# RELAY.net
KiCad netlist of a schematic drawn in Altium Designer
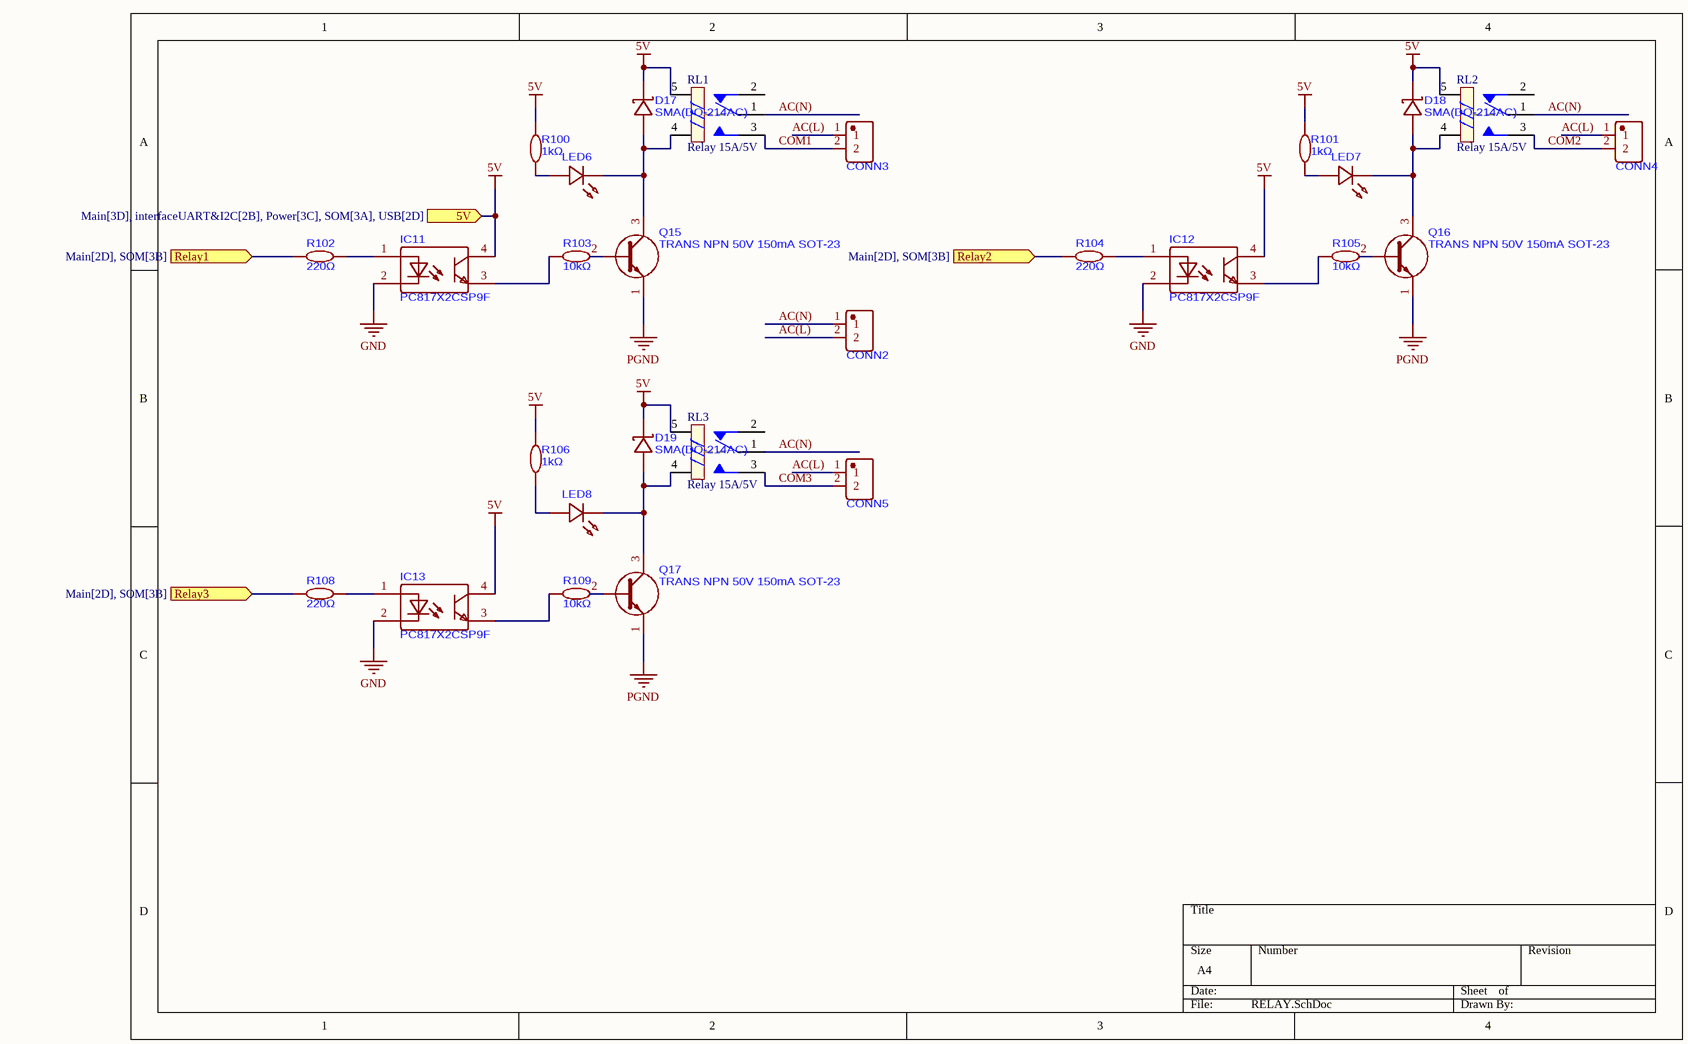
[diagram p0: RELAY.SchDoc]

(export (version "E")
  (design (tool "Eeschema 10.0.6"))
  (components
    (comp (ref "CONN2")
      (value "TERM BLK 2POS 5mm TH")
      (footprint "CONN-TH_P5.00_KF128-5.0-2P")
      (libsource (lib "Schlib2") (part "KF128-5.0-2P"))
    )
    (comp (ref "CONN3")
      (value "TERM BLK 2POS 5mm TH")
      (footprint "CONN-TH_P5.00_KF128-5.0-2P")
      (libsource (lib "Schlib2") (part "KF128-5.0-2P"))
    )
    (comp (ref "CONN4")
      (value "TERM BLK 2POS 5mm TH")
      (footprint "CONN-TH_P5.00_KF128-5.0-2P")
      (libsource (lib "Schlib2") (part "KF128-5.0-2P"))
    )
    (comp (ref "CONN5")
      (value "TERM BLK 2POS 5mm TH")
      (footprint "CONN-TH_P5.00_KF128-5.0-2P")
      (libsource (lib "Schlib2") (part "KF128-5.0-2P"))
    )
    (comp (ref "D17")
      (value "SMA(DO-214AC)")
      (footprint "SMA_L4.4-W2.6-LS5.0-RD")
      (description "80A 40V 500mV@3A 3A SMA(DO-214AC) Single Diodes ROHS")
      (libsource (lib "Schlib2") (part "B340A-13-F"))
    )
    (comp (ref "D18")
      (value "SMA(DO-214AC)")
      (footprint "SMA_L4.4-W2.6-LS5.0-RD")
      (description "80A 40V 500mV@3A 3A SMA(DO-214AC) Single Diodes ROHS")
      (libsource (lib "Schlib2") (part "B340A-13-F"))
    )
    (comp (ref "D19")
      (value "SMA(DO-214AC)")
      (footprint "SMA_L4.4-W2.6-LS5.0-RD")
      (description "80A 40V 500mV@3A 3A SMA(DO-214AC) Single Diodes ROHS")
      (libsource (lib "Schlib2") (part "B340A-13-F"))
    )
    (comp (ref "IC11")
      (value "PC817X2CSP9F")
      (footprint "smd pc817")
      (description "50mA 200mV@20mA,1mA 80V 6V DC SMD-4P Transistor, Photovoltaic Output Optoisolators RoHS")
      (libsource (lib "Schlib2") (part "PC817X2CSP9F"))
    )
    (comp (ref "IC12")
      (value "PC817X2CSP9F")
      (footprint "smd pc817")
      (description "50mA 200mV@20mA,1mA 80V 6V DC SMD-4P Transistor, Photovoltaic Output Optoisolators RoHS")
      (libsource (lib "Schlib2") (part "PC817X2CSP9F"))
    )
    (comp (ref "IC13")
      (value "PC817X2CSP9F")
      (footprint "smd pc817")
      (description "50mA 200mV@20mA,1mA 80V 6V DC SMD-4P Transistor, Photovoltaic Output Optoisolators RoHS")
      (libsource (lib "Schlib2") (part "PC817X2CSP9F"))
    )
    (comp (ref "LED6")
      (value "XL-1608SURC-06")
      (footprint "LED0603-RD_RED")
      (description "20mA 2.3V Red 50mW 0603 LED Indication - Discrete ROHS")
      (libsource (lib "Schlib2") (part "XL-1608SURC-06"))
    )
    (comp (ref "LED7")
      (value "XL-1608SURC-06")
      (footprint "LED0603-RD_RED")
      (description "20mA 2.3V Red 50mW 0603 LED Indication - Discrete ROHS")
      (libsource (lib "Schlib2") (part "XL-1608SURC-06"))
    )
    (comp (ref "LED8")
      (value "XL-1608SURC-06")
      (footprint "LED0603-RD_RED")
      (description "20mA 2.3V Red 50mW 0603 LED Indication - Discrete ROHS")
      (libsource (lib "Schlib2") (part "XL-1608SURC-06"))
    )
    (comp (ref "Q15")
      (value "TRANS NPN 50V 150mA SOT-23")
      (footprint "SOT-23-3_L2.9-W1.3-P1.90-LS2.4-BR")
      (description "200mW 50V 150mA NPN SOT-23 Single Bipolar Transistors RoHS")
      (libsource (lib "Schlib2") (part "2SC1815"))
    )
    (comp (ref "Q16")
      (value "TRANS NPN 50V 150mA SOT-23")
      (footprint "SOT-23-3_L2.9-W1.3-P1.90-LS2.4-BR")
      (description "200mW 50V 150mA NPN SOT-23 Single Bipolar Transistors RoHS")
      (libsource (lib "Schlib2") (part "2SC1815"))
    )
    (comp (ref "Q17")
      (value "TRANS NPN 50V 150mA SOT-23")
      (footprint "SOT-23-3_L2.9-W1.3-P1.90-LS2.4-BR")
      (description "200mW 50V 150mA NPN SOT-23 Single Bipolar Transistors RoHS")
      (libsource (lib "Schlib2") (part "2SC1815"))
    )
    (comp (ref "R100")
      (value "1kΩ")
      (footprint "R0603")
      (description "100mW 1kΩ 50V ±100ppm/℃ Thick Film Resistor ±5% 0603 Chip Resistor - Surface Mount ROHS")
      (libsource (lib "Schlib2") (part "RMC 0603 1K J N"))
    )
    (comp (ref "R101")
      (value "1kΩ")
      (footprint "R0603")
      (description "100mW 1kΩ 50V ±100ppm/℃ Thick Film Resistor ±5% 0603 Chip Resistor - Surface Mount ROHS")
      (libsource (lib "Schlib2") (part "RMC 0603 1K J N"))
    )
    (comp (ref "R102")
      (value "220Ω")
      (footprint "R0603")
      (description "100mW 220Ω 75V ±100ppm/℃ Thick Film Resistor ±1% 0603 Chip Resistor - Surface Mount RoHS")
      (libsource (lib "Schlib2") (part "RC0603FR-07220RL"))
    )
    (comp (ref "R103")
      (value "10kΩ")
      (footprint "R0603")
      (description "100mW 10kΩ 75V ±100ppm/℃ Thick Film Resistor ±1% 0603 Chip Resistor - Surface Mount ROHS")
      (libsource (lib "Schlib2") (part "RC0603FR-0710KL"))
    )
    (comp (ref "R104")
      (value "220Ω")
      (footprint "R0603")
      (description "100mW 220Ω 75V ±100ppm/℃ Thick Film Resistor ±1% 0603 Chip Resistor - Surface Mount RoHS")
      (libsource (lib "Schlib2") (part "RC0603FR-07220RL"))
    )
    (comp (ref "R105")
      (value "10kΩ")
      (footprint "R0603")
      (description "100mW 10kΩ 75V ±100ppm/℃ Thick Film Resistor ±1% 0603 Chip Resistor - Surface Mount ROHS")
      (libsource (lib "Schlib2") (part "RC0603FR-0710KL"))
    )
    (comp (ref "R106")
      (value "1kΩ")
      (footprint "R0603")
      (description "100mW 1kΩ 50V ±100ppm/℃ Thick Film Resistor ±5% 0603 Chip Resistor - Surface Mount ROHS")
      (libsource (lib "Schlib2") (part "RMC 0603 1K J N"))
    )
    (comp (ref "R108")
      (value "220Ω")
      (footprint "R0603")
      (description "100mW 220Ω 75V ±100ppm/℃ Thick Film Resistor ±1% 0603 Chip Resistor - Surface Mount RoHS")
      (libsource (lib "Schlib2") (part "RC0603FR-07220RL"))
    )
    (comp (ref "R109")
      (value "10kΩ")
      (footprint "R0603")
      (description "100mW 10kΩ 75V ±100ppm/℃ Thick Film Resistor ±1% 0603 Chip Resistor - Surface Mount ROHS")
      (libsource (lib "Schlib2") (part "RC0603FR-0710KL"))
    )
    (comp (ref "RL1")
      (value "Relay 15A/5V")
      (footprint "RL-5V-15A")
      (description "Relay SPDT,10A - 5VDC 5 Pin")
      (libsource (lib "Schlib2") (part "SRD-05VDC-SL-C"))
    )
    (comp (ref "RL2")
      (value "Relay 15A/5V")
      (footprint "RL-5V-15A")
      (description "Relay SPDT,10A - 5VDC 5 Pin")
      (libsource (lib "Schlib2") (part "SRD-05VDC-SL-C"))
    )
    (comp (ref "RL3")
      (value "Relay 15A/5V")
      (footprint "RL-5V-15A")
      (description "Relay SPDT,10A - 5VDC 5 Pin")
      (libsource (lib "Schlib2") (part "SRD-05VDC-SL-C"))
    )
  )
  (nets
    (net (code "1") (name "/AC(L)") (class "Default")
      (node (ref "CONN2") (pin "2") (pinfunction "2_2") (pintype "passive"))
      (node (ref "CONN3") (pin "1") (pinfunction "1_1") (pintype "passive"))
      (node (ref "CONN4") (pin "1") (pinfunction "1_1") (pintype "passive"))
      (node (ref "CONN5") (pin "1") (pinfunction "1_1") (pintype "passive"))
    )
    (net (code "2") (name "/AC(N)") (class "Default")
      (node (ref "CONN2") (pin "1") (pinfunction "1_1") (pintype "passive"))
      (node (ref "RL1") (pin "1") (pinfunction "1_1") (pintype "passive"))
      (node (ref "RL2") (pin "1") (pinfunction "1_1") (pintype "passive"))
      (node (ref "RL3") (pin "1") (pinfunction "1_1") (pintype "passive"))
    )
    (net (code "3") (name "/COM1") (class "Default")
      (node (ref "CONN3") (pin "2") (pinfunction "2_2") (pintype "passive"))
      (node (ref "RL1") (pin "3") (pinfunction "3_3") (pintype "passive"))
    )
    (net (code "4") (name "/COM2") (class "Default")
      (node (ref "CONN4") (pin "2") (pinfunction "2_2") (pintype "passive"))
      (node (ref "RL2") (pin "3") (pinfunction "3_3") (pintype "passive"))
    )
    (net (code "5") (name "/COM3") (class "Default")
      (node (ref "CONN5") (pin "2") (pinfunction "2_2") (pintype "passive"))
      (node (ref "RL3") (pin "3") (pinfunction "3_3") (pintype "passive"))
    )
    (net (code "6") (name "/Relay1") (class "Default")
      (node (ref "R102") (pin "1") (pinfunction "1_1") (pintype "passive"))
    )
    (net (code "7") (name "/Relay2") (class "Default")
      (node (ref "R104") (pin "1") (pinfunction "1_1") (pintype "passive"))
    )
    (net (code "8") (name "/Relay3") (class "Default")
      (node (ref "R108") (pin "1") (pinfunction "1_1") (pintype "passive"))
    )
    (net (code "9") (name "5V") (class "Default")
      (node (ref "D17") (pin "1") (pinfunction "K_1") (pintype "passive"))
      (node (ref "D18") (pin "1") (pinfunction "K_1") (pintype "passive"))
      (node (ref "D19") (pin "1") (pinfunction "K_1") (pintype "passive"))
      (node (ref "IC11") (pin "4") (pinfunction "COL_4") (pintype "passive"))
      (node (ref "IC12") (pin "4") (pinfunction "COL_4") (pintype "passive"))
      (node (ref "IC13") (pin "4") (pinfunction "COL_4") (pintype "passive"))
      (node (ref "R100") (pin "2") (pinfunction "2_2") (pintype "passive"))
      (node (ref "R101") (pin "2") (pinfunction "2_2") (pintype "passive"))
      (node (ref "R106") (pin "2") (pinfunction "2_2") (pintype "passive"))
      (node (ref "RL1") (pin "5") (pinfunction "5_5") (pintype "passive"))
      (node (ref "RL2") (pin "5") (pinfunction "5_5") (pintype "passive"))
      (node (ref "RL3") (pin "5") (pinfunction "5_5") (pintype "passive"))
    )
    (net (code "10") (name "GND") (class "Default")
      (node (ref "IC11") (pin "2") (pinfunction "CAT_2") (pintype "passive"))
      (node (ref "IC12") (pin "2") (pinfunction "CAT_2") (pintype "passive"))
      (node (ref "IC13") (pin "2") (pinfunction "CAT_2") (pintype "passive"))
    )
    (net (code "11") (name "Net-(D17-A)") (class "Default")
      (node (ref "D17") (pin "2") (pinfunction "A_2") (pintype "passive"))
      (node (ref "LED6") (pin "1") (pinfunction "K_1") (pintype "passive"))
      (node (ref "Q15") (pin "3") (pintype "passive"))
      (node (ref "RL1") (pin "4") (pinfunction "4_4") (pintype "passive"))
    )
    (net (code "12") (name "Net-(D18-A)") (class "Default")
      (node (ref "D18") (pin "2") (pinfunction "A_2") (pintype "passive"))
      (node (ref "LED7") (pin "1") (pinfunction "K_1") (pintype "passive"))
      (node (ref "Q16") (pin "3") (pintype "passive"))
      (node (ref "RL2") (pin "4") (pinfunction "4_4") (pintype "passive"))
    )
    (net (code "13") (name "Net-(D19-A)") (class "Default")
      (node (ref "D19") (pin "2") (pinfunction "A_2") (pintype "passive"))
      (node (ref "LED8") (pin "1") (pinfunction "K_1") (pintype "passive"))
      (node (ref "Q17") (pin "3") (pintype "passive"))
      (node (ref "RL3") (pin "4") (pinfunction "4_4") (pintype "passive"))
    )
    (net (code "14") (name "Net-(IC11-AN)") (class "Default")
      (node (ref "IC11") (pin "1") (pinfunction "AN_1") (pintype "passive"))
      (node (ref "R102") (pin "2") (pinfunction "2_2") (pintype "passive"))
    )
    (net (code "15") (name "Net-(IC11-EM)") (class "Default")
      (node (ref "IC11") (pin "3") (pinfunction "EM_3") (pintype "passive"))
      (node (ref "R103") (pin "1") (pinfunction "1_1") (pintype "passive"))
    )
    (net (code "16") (name "Net-(IC12-AN)") (class "Default")
      (node (ref "IC12") (pin "1") (pinfunction "AN_1") (pintype "passive"))
      (node (ref "R104") (pin "2") (pinfunction "2_2") (pintype "passive"))
    )
    (net (code "17") (name "Net-(IC12-EM)") (class "Default")
      (node (ref "IC12") (pin "3") (pinfunction "EM_3") (pintype "passive"))
      (node (ref "R105") (pin "1") (pinfunction "1_1") (pintype "passive"))
    )
    (net (code "18") (name "Net-(IC13-AN)") (class "Default")
      (node (ref "IC13") (pin "1") (pinfunction "AN_1") (pintype "passive"))
      (node (ref "R108") (pin "2") (pinfunction "2_2") (pintype "passive"))
    )
    (net (code "19") (name "Net-(IC13-EM)") (class "Default")
      (node (ref "IC13") (pin "3") (pinfunction "EM_3") (pintype "passive"))
      (node (ref "R109") (pin "1") (pinfunction "1_1") (pintype "passive"))
    )
    (net (code "20") (name "Net-(LED6-A)") (class "Default")
      (node (ref "LED6") (pin "2") (pinfunction "A_2") (pintype "passive"))
      (node (ref "R100") (pin "1") (pinfunction "1_1") (pintype "passive"))
    )
    (net (code "21") (name "Net-(LED7-A)") (class "Default")
      (node (ref "LED7") (pin "2") (pinfunction "A_2") (pintype "passive"))
      (node (ref "R101") (pin "1") (pinfunction "1_1") (pintype "passive"))
    )
    (net (code "22") (name "Net-(LED8-A)") (class "Default")
      (node (ref "LED8") (pin "2") (pinfunction "A_2") (pintype "passive"))
      (node (ref "R106") (pin "1") (pinfunction "1_1") (pintype "passive"))
    )
    (net (code "23") (name "Net-(Q15-Pad2)") (class "Default")
      (node (ref "Q15") (pin "2") (pintype "passive"))
      (node (ref "R103") (pin "2") (pinfunction "2_2") (pintype "passive"))
    )
    (net (code "24") (name "Net-(Q16-Pad2)") (class "Default")
      (node (ref "Q16") (pin "2") (pintype "passive"))
      (node (ref "R105") (pin "2") (pinfunction "2_2") (pintype "passive"))
    )
    (net (code "25") (name "Net-(Q17-Pad2)") (class "Default")
      (node (ref "Q17") (pin "2") (pintype "passive"))
      (node (ref "R109") (pin "2") (pinfunction "2_2") (pintype "passive"))
    )
    (net (code "26") (name "PGND") (class "Default")
      (node (ref "Q15") (pin "1") (pintype "passive"))
      (node (ref "Q16") (pin "1") (pintype "passive"))
      (node (ref "Q17") (pin "1") (pintype "passive"))
    )
    (net (code "27") (name "unconnected-(RL1-Pad2)") (class "Default")
      (node (ref "RL1") (pin "2") (pinfunction "2_2") (pintype "passive"))
    )
    (net (code "28") (name "unconnected-(RL2-Pad2)") (class "Default")
      (node (ref "RL2") (pin "2") (pinfunction "2_2") (pintype "passive"))
    )
    (net (code "29") (name "unconnected-(RL3-Pad2)") (class "Default")
      (node (ref "RL3") (pin "2") (pinfunction "2_2") (pintype "passive"))
    )
  )
)
